# Bit_Reactor_modular_v1_0.net
KiCad netlist of a schematic drawn in EAGLE
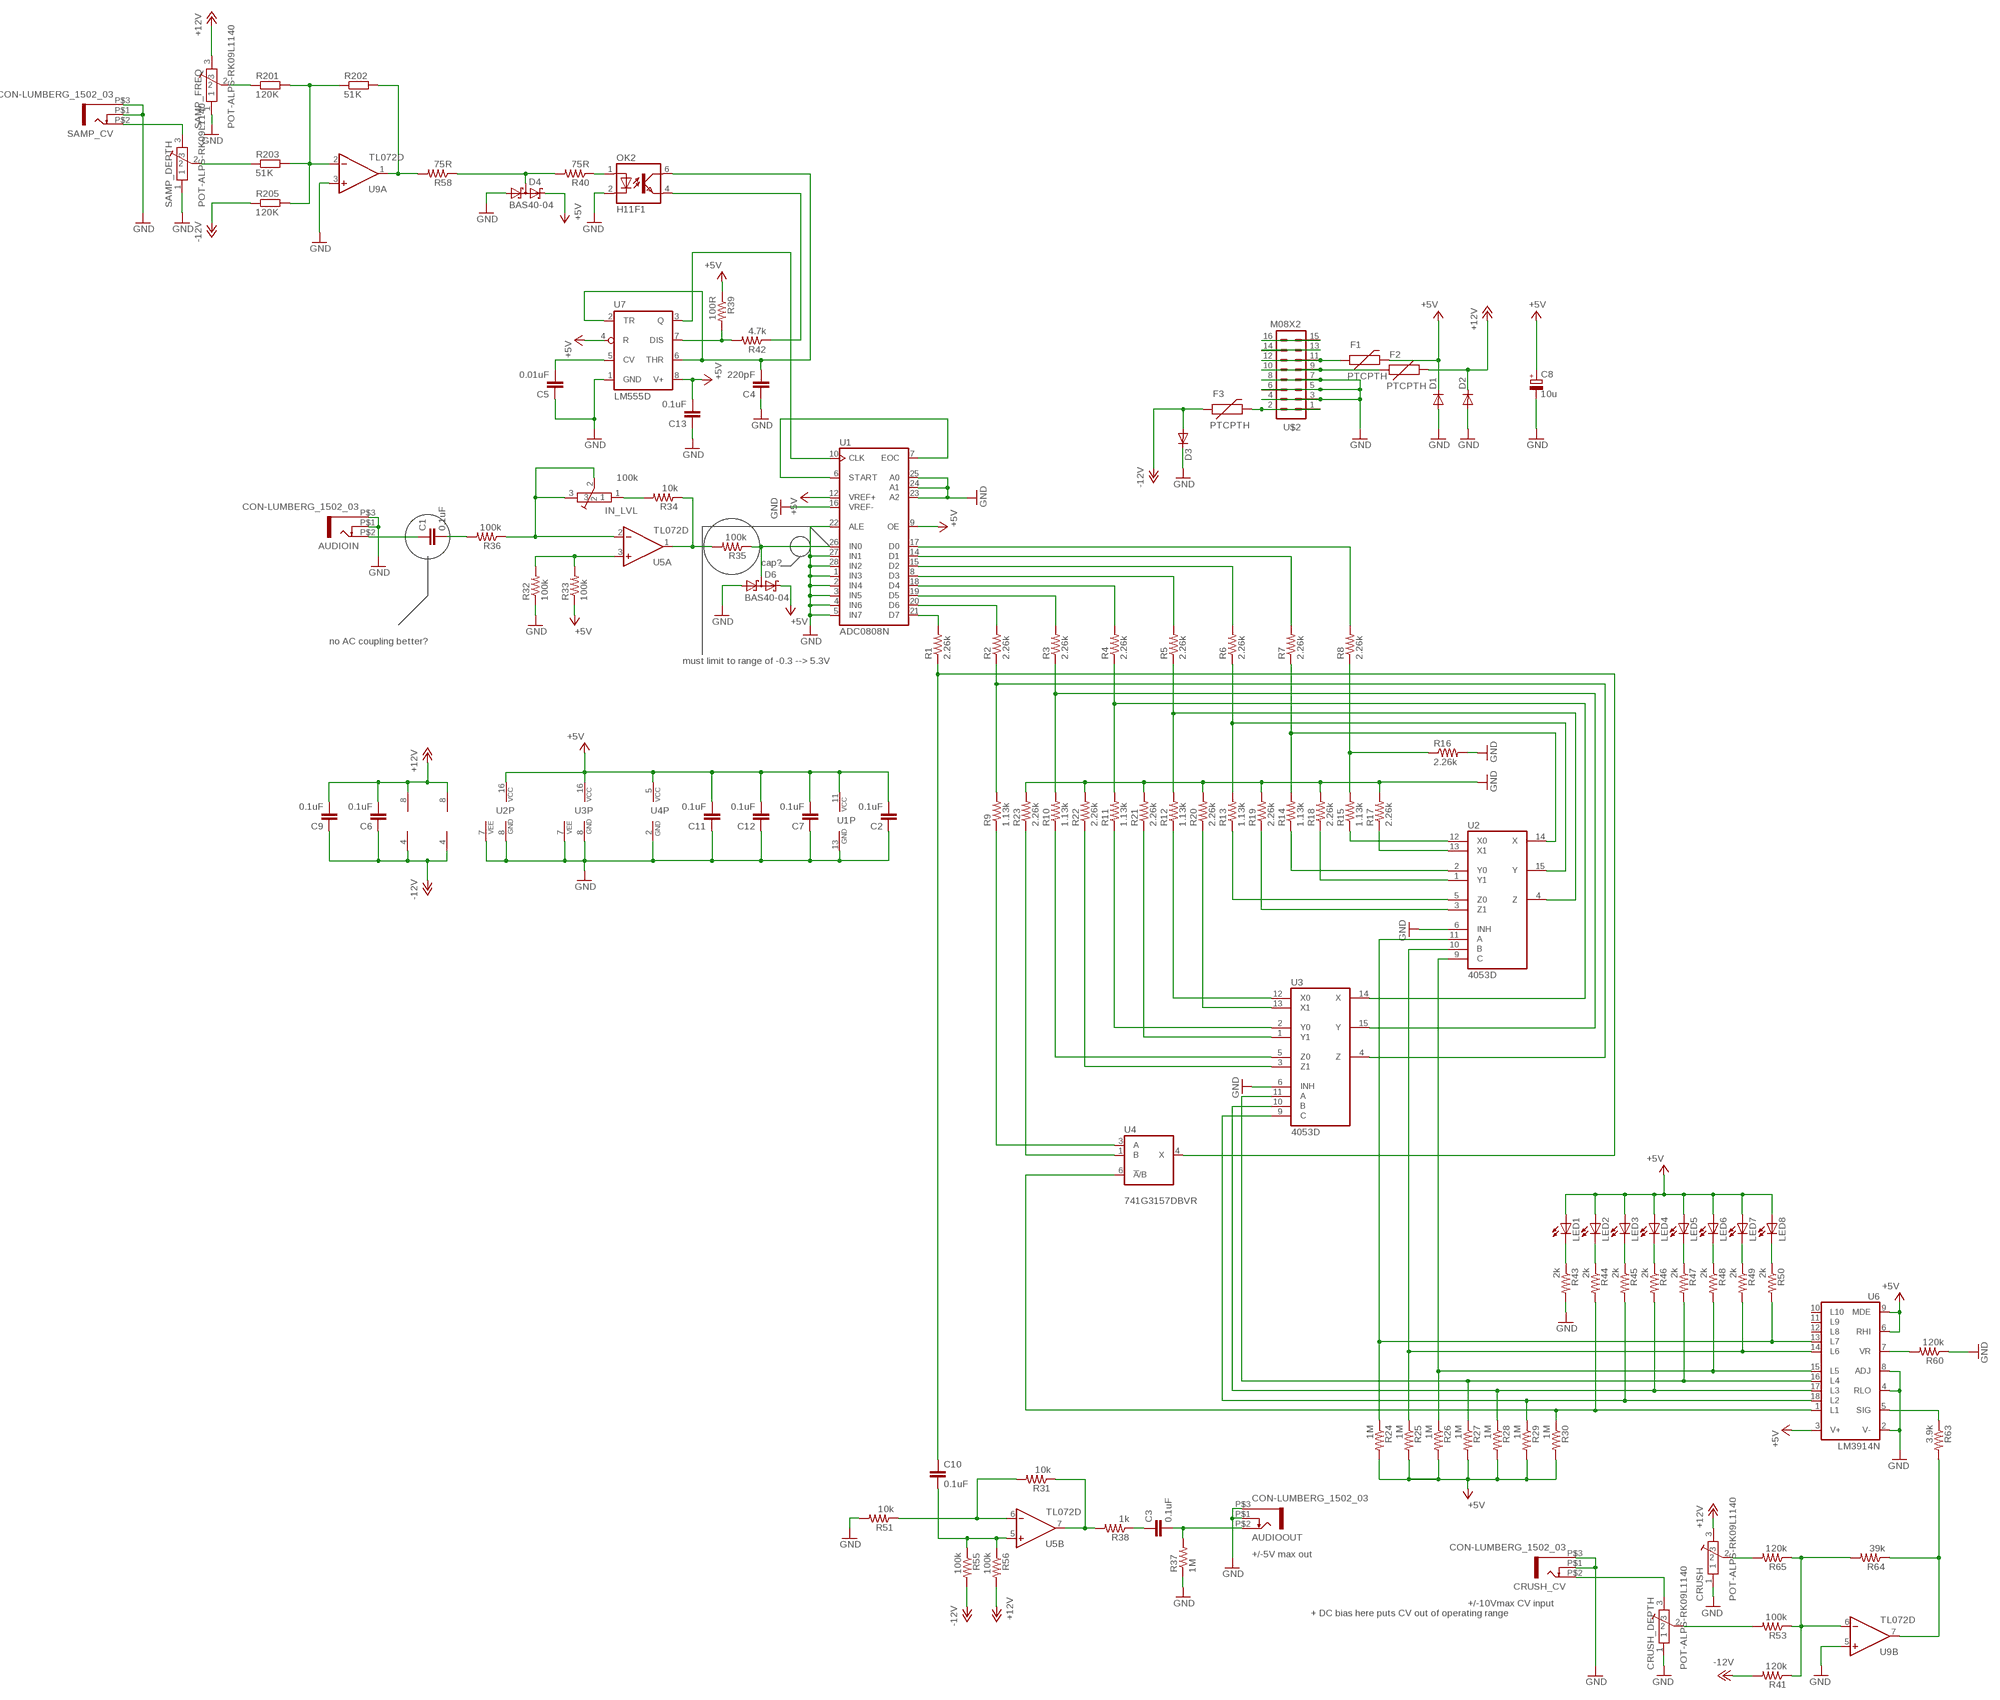
[diagram p0: schematic, sheet 1]

(export (version "E")
  (design (tool "Eeschema 10.0.6"))
  (components
    (comp (ref "AUDIOIN")
      (value "CON-LUMBERG_1502_03")
      (footprint "eagle-import:CON-LUMBERG_1502_03")
      (libsource (lib "eagle-import") (part "CON-LUMBERG_1502_03"))
    )
    (comp (ref "AUDIOOUT")
      (value "CON-LUMBERG_1502_03")
      (footprint "eagle-import:CON-LUMBERG_1502_03")
      (libsource (lib "eagle-import") (part "CON-LUMBERG_1502_03"))
    )
    (comp (ref "C1")
      (value "0.1uF")
      (footprint "eagle-import:C025-030X050")
      (libsource (lib "eagle-import") (part "C-EU025-030X050"))
    )
    (comp (ref "C2")
      (value "0.1uF")
      (footprint "eagle-import:C025-030X050")
      (libsource (lib "eagle-import") (part "C-EU025-030X050"))
    )
    (comp (ref "C3")
      (value "0.1uF")
      (footprint "eagle-import:C025-025X050")
      (libsource (lib "eagle-import") (part "C-EU025-025X050"))
    )
    (comp (ref "C4")
      (value "220pF")
      (footprint "eagle-import:C025-030X050")
      (libsource (lib "eagle-import") (part "C-EU025-030X050"))
    )
    (comp (ref "C5")
      (value "0.01uF")
      (footprint "eagle-import:C025-030X050")
      (libsource (lib "eagle-import") (part "C-EU025-030X050"))
    )
    (comp (ref "C6")
      (value "0.1uF")
      (footprint "eagle-import:C025-030X050")
      (libsource (lib "eagle-import") (part "C-EU025-030X050"))
    )
    (comp (ref "C7")
      (value "0.1uF")
      (footprint "eagle-import:C025-030X050")
      (libsource (lib "eagle-import") (part "C-EU025-030X050"))
    )
    (comp (ref "C8")
      (value "10u")
      (footprint "eagle-import:E5-6")
      (libsource (lib "eagle-import") (part "CPOL-EUE5-6"))
    )
    (comp (ref "C9")
      (value "0.1uF")
      (footprint "eagle-import:C025-030X050")
      (libsource (lib "eagle-import") (part "C-EU025-030X050"))
    )
    (comp (ref "C10")
      (value "0.1uF")
      (footprint "eagle-import:C025-030X050")
      (libsource (lib "eagle-import") (part "C-EU025-030X050"))
    )
    (comp (ref "C11")
      (value "0.1uF")
      (footprint "eagle-import:C025-030X050")
      (libsource (lib "eagle-import") (part "C-EU025-030X050"))
    )
    (comp (ref "C12")
      (value "0.1uF")
      (footprint "eagle-import:C025-030X050")
      (libsource (lib "eagle-import") (part "C-EU025-030X050"))
    )
    (comp (ref "C13")
      (value "0.1uF")
      (footprint "eagle-import:C025-030X050")
      (libsource (lib "eagle-import") (part "C-EU025-030X050"))
    )
    (comp (ref "CRUSH")
      (value "POT-ALPS-RK09L1140")
      (footprint "eagle-import:POT-ALPS-RK09L1140")
      (libsource (lib "eagle-import") (part "POT-ALPS-RK09L1140"))
    )
    (comp (ref "CRUSH_CV")
      (value "CON-LUMBERG_1502_03")
      (footprint "eagle-import:CON-LUMBERG_1502_03")
      (libsource (lib "eagle-import") (part "CON-LUMBERG_1502_03"))
    )
    (comp (ref "CRUSH_DEPTH")
      (value "POT-ALPS-RK09L1140")
      (footprint "eagle-import:POT-ALPS-RK09L1140")
      (libsource (lib "eagle-import") (part "POT-ALPS-RK09L1140"))
    )
    (comp (ref "D1")
      (value "DIODE1N4001")
      (footprint "eagle-import:DIODE-1N4001")
      (libsource (lib "eagle-import") (part "DIODE1N4001"))
    )
    (comp (ref "D2")
      (value "DIODE1N4001")
      (footprint "eagle-import:DIODE-1N4001")
      (libsource (lib "eagle-import") (part "DIODE1N4001"))
    )
    (comp (ref "D3")
      (value "DIODE1N4001")
      (footprint "eagle-import:DIODE-1N4001")
      (libsource (lib "eagle-import") (part "DIODE1N4001"))
    )
    (comp (ref "D4")
      (value "BAS40-04")
      (footprint "eagle-import:SOT23")
      (libsource (lib "eagle-import") (part "BAS40-04"))
    )
    (comp (ref "D6")
      (value "BAS40-04")
      (footprint "eagle-import:SOT23")
      (libsource (lib "eagle-import") (part "BAS40-04"))
    )
    (comp (ref "F1")
      (value "PTCPTH")
      (footprint "eagle-import:PTC")
      (libsource (lib "eagle-import") (part "PTCPTH"))
    )
    (comp (ref "F2")
      (value "PTCPTH")
      (footprint "eagle-import:PTC")
      (libsource (lib "eagle-import") (part "PTCPTH"))
    )
    (comp (ref "F3")
      (value "PTCPTH")
      (footprint "eagle-import:PTC")
      (libsource (lib "eagle-import") (part "PTCPTH"))
    )
    (comp (ref "IN_LVL")
      (value "100k")
      (footprint "eagle-import:POT-ALPS-RK09L1140")
      (libsource (lib "eagle-import") (part "POT-ALPS-RK09L1140"))
    )
    (comp (ref "LED1")
      (value "LED3MM")
      (footprint "eagle-import:LED3MM")
      (libsource (lib "eagle-import") (part "LED3MM"))
    )
    (comp (ref "LED2")
      (value "LED3MM")
      (footprint "eagle-import:LED3MM")
      (libsource (lib "eagle-import") (part "LED3MM"))
    )
    (comp (ref "LED3")
      (value "LED3MM")
      (footprint "eagle-import:LED3MM")
      (libsource (lib "eagle-import") (part "LED3MM"))
    )
    (comp (ref "LED4")
      (value "LED3MM")
      (footprint "eagle-import:LED3MM")
      (libsource (lib "eagle-import") (part "LED3MM"))
    )
    (comp (ref "LED5")
      (value "LED3MM")
      (footprint "eagle-import:LED3MM")
      (libsource (lib "eagle-import") (part "LED3MM"))
    )
    (comp (ref "LED6")
      (value "LED3MM")
      (footprint "eagle-import:LED3MM")
      (libsource (lib "eagle-import") (part "LED3MM"))
    )
    (comp (ref "LED7")
      (value "LED3MM")
      (footprint "eagle-import:LED3MM")
      (libsource (lib "eagle-import") (part "LED3MM"))
    )
    (comp (ref "LED8")
      (value "LED3MM")
      (footprint "eagle-import:LED3MM")
      (libsource (lib "eagle-import") (part "LED3MM"))
    )
    (comp (ref "OK2")
      (value "H11F1")
      (footprint "eagle-import:DIL05")
      (fields (field (name "OC_FARNELL") "unknown") (field (name "OC_NEWARK") "unknown"))
      (libsource (lib "eagle-import") (part "H11F1"))
    )
    (comp (ref "R1")
      (value "2.26k")
      (footprint "eagle-import:R0805W")
      (libsource (lib "eagle-import") (part "R-US_R0805W"))
    )
    (comp (ref "R2")
      (value "2.26k")
      (footprint "eagle-import:R0805W")
      (libsource (lib "eagle-import") (part "R-US_R0805W"))
    )
    (comp (ref "R3")
      (value "2.26k")
      (footprint "eagle-import:R0805W")
      (libsource (lib "eagle-import") (part "R-US_R0805W"))
    )
    (comp (ref "R4")
      (value "2.26k")
      (footprint "eagle-import:R0805W")
      (libsource (lib "eagle-import") (part "R-US_R0805W"))
    )
    (comp (ref "R5")
      (value "2.26k")
      (footprint "eagle-import:R0805W")
      (libsource (lib "eagle-import") (part "R-US_R0805W"))
    )
    (comp (ref "R6")
      (value "2.26k")
      (footprint "eagle-import:R0805W")
      (libsource (lib "eagle-import") (part "R-US_R0805W"))
    )
    (comp (ref "R7")
      (value "2.26k")
      (footprint "eagle-import:R0805W")
      (libsource (lib "eagle-import") (part "R-US_R0805W"))
    )
    (comp (ref "R8")
      (value "2.26k")
      (footprint "eagle-import:R0805W")
      (libsource (lib "eagle-import") (part "R-US_R0805W"))
    )
    (comp (ref "R9")
      (value "1.13k")
      (footprint "eagle-import:R0805W")
      (libsource (lib "eagle-import") (part "R-US_R0805W"))
    )
    (comp (ref "R10")
      (value "1.13k")
      (footprint "eagle-import:R0805W")
      (libsource (lib "eagle-import") (part "R-US_R0805W"))
    )
    (comp (ref "R11")
      (value "1.13k")
      (footprint "eagle-import:R0805W")
      (libsource (lib "eagle-import") (part "R-US_R0805W"))
    )
    (comp (ref "R12")
      (value "1.13k")
      (footprint "eagle-import:R0805W")
      (libsource (lib "eagle-import") (part "R-US_R0805W"))
    )
    (comp (ref "R13")
      (value "1.13k")
      (footprint "eagle-import:R0805W")
      (libsource (lib "eagle-import") (part "R-US_R0805W"))
    )
    (comp (ref "R14")
      (value "1.13k")
      (footprint "eagle-import:R0805W")
      (libsource (lib "eagle-import") (part "R-US_R0805W"))
    )
    (comp (ref "R15")
      (value "1.13k")
      (footprint "eagle-import:R0805W")
      (libsource (lib "eagle-import") (part "R-US_R0805W"))
    )
    (comp (ref "R16")
      (value "2.26k")
      (footprint "eagle-import:R0805W")
      (libsource (lib "eagle-import") (part "R-US_R0805W"))
    )
    (comp (ref "R17")
      (value "2.26k")
      (footprint "eagle-import:R0805W")
      (libsource (lib "eagle-import") (part "R-US_R0805W"))
    )
    (comp (ref "R18")
      (value "2.26k")
      (footprint "eagle-import:R0805W")
      (libsource (lib "eagle-import") (part "R-US_R0805W"))
    )
    (comp (ref "R19")
      (value "2.26k")
      (footprint "eagle-import:R0805W")
      (libsource (lib "eagle-import") (part "R-US_R0805W"))
    )
    (comp (ref "R20")
      (value "2.26k")
      (footprint "eagle-import:R0805W")
      (libsource (lib "eagle-import") (part "R-US_R0805W"))
    )
    (comp (ref "R21")
      (value "2.26k")
      (footprint "eagle-import:R0805W")
      (libsource (lib "eagle-import") (part "R-US_R0805W"))
    )
    (comp (ref "R22")
      (value "2.26k")
      (footprint "eagle-import:R0805W")
      (libsource (lib "eagle-import") (part "R-US_R0805W"))
    )
    (comp (ref "R23")
      (value "2.26k")
      (footprint "eagle-import:R0805W")
      (libsource (lib "eagle-import") (part "R-US_R0805W"))
    )
    (comp (ref "R24")
      (value "1M")
      (footprint "eagle-import:R0402")
      (libsource (lib "eagle-import") (part "R-US_R0402"))
    )
    (comp (ref "R25")
      (value "1M")
      (footprint "eagle-import:R0402")
      (libsource (lib "eagle-import") (part "R-US_R0402"))
    )
    (comp (ref "R26")
      (value "1M")
      (footprint "eagle-import:R0402")
      (libsource (lib "eagle-import") (part "R-US_R0402"))
    )
    (comp (ref "R27")
      (value "1M")
      (footprint "eagle-import:R0402")
      (libsource (lib "eagle-import") (part "R-US_R0402"))
    )
    (comp (ref "R28")
      (value "1M")
      (footprint "eagle-import:R0402")
      (libsource (lib "eagle-import") (part "R-US_R0402"))
    )
    (comp (ref "R29")
      (value "1M")
      (footprint "eagle-import:R0402")
      (libsource (lib "eagle-import") (part "R-US_R0402"))
    )
    (comp (ref "R30")
      (value "1M")
      (footprint "eagle-import:R0402")
      (libsource (lib "eagle-import") (part "R-US_R0402"))
    )
    (comp (ref "R31")
      (value "10k")
      (footprint "eagle-import:0207_10")
      (libsource (lib "eagle-import") (part "R-US_0207/10"))
    )
    (comp (ref "R32")
      (value "100k")
      (footprint "eagle-import:0207_10")
      (libsource (lib "eagle-import") (part "R-US_0207/10"))
    )
    (comp (ref "R33")
      (value "100k")
      (footprint "eagle-import:0207_10")
      (libsource (lib "eagle-import") (part "R-US_0207/10"))
    )
    (comp (ref "R34")
      (value "10k")
      (footprint "eagle-import:0207_10")
      (libsource (lib "eagle-import") (part "R-US_0207/10"))
    )
    (comp (ref "R35")
      (value "100k")
      (footprint "eagle-import:0207_10")
      (libsource (lib "eagle-import") (part "R-US_0207/10"))
    )
    (comp (ref "R36")
      (value "100k")
      (footprint "eagle-import:0207_10")
      (libsource (lib "eagle-import") (part "R-US_0207/10"))
    )
    (comp (ref "R37")
      (value "1M")
      (footprint "eagle-import:R0402")
      (libsource (lib "eagle-import") (part "R-US_R0402"))
    )
    (comp (ref "R38")
      (value "1k")
      (footprint "eagle-import:0207_10")
      (libsource (lib "eagle-import") (part "R-US_0207/10"))
    )
    (comp (ref "R39")
      (value "100R")
      (footprint "eagle-import:0207_10")
      (libsource (lib "eagle-import") (part "R-US_0207/10"))
    )
    (comp (ref "R40")
      (value "75R")
      (footprint "eagle-import:0207_10")
      (libsource (lib "eagle-import") (part "R-US_0207/10"))
    )
    (comp (ref "R41")
      (value "120k")
      (footprint "eagle-import:0207_10")
      (libsource (lib "eagle-import") (part "R-US_0207/10"))
    )
    (comp (ref "R42")
      (value "4.7k")
      (footprint "eagle-import:0207_10")
      (libsource (lib "eagle-import") (part "R-US_0207/10"))
    )
    (comp (ref "R43")
      (value "2k")
      (footprint "eagle-import:0207_7")
      (libsource (lib "eagle-import") (part "R-US_0207/7"))
    )
    (comp (ref "R44")
      (value "2k")
      (footprint "eagle-import:0207_7")
      (libsource (lib "eagle-import") (part "R-US_0207/7"))
    )
    (comp (ref "R45")
      (value "2k")
      (footprint "eagle-import:0207_7")
      (libsource (lib "eagle-import") (part "R-US_0207/7"))
    )
    (comp (ref "R46")
      (value "2k")
      (footprint "eagle-import:0207_7")
      (libsource (lib "eagle-import") (part "R-US_0207/7"))
    )
    (comp (ref "R47")
      (value "2k")
      (footprint "eagle-import:0207_7")
      (libsource (lib "eagle-import") (part "R-US_0207/7"))
    )
    (comp (ref "R48")
      (value "2k")
      (footprint "eagle-import:0207_10")
      (libsource (lib "eagle-import") (part "R-US_0207/10"))
    )
    (comp (ref "R49")
      (value "2k")
      (footprint "eagle-import:0207_7")
      (libsource (lib "eagle-import") (part "R-US_0207/7"))
    )
    (comp (ref "R50")
      (value "2k")
      (footprint "eagle-import:0207_7")
      (libsource (lib "eagle-import") (part "R-US_0207/7"))
    )
    (comp (ref "R51")
      (value "10k")
      (footprint "eagle-import:0207_10")
      (libsource (lib "eagle-import") (part "R-US_0207/10"))
    )
    (comp (ref "R53")
      (value "100k")
      (footprint "eagle-import:0207_10")
      (libsource (lib "eagle-import") (part "R-US_0207/10"))
    )
    (comp (ref "R55")
      (value "100k")
      (footprint "eagle-import:0207_10")
      (libsource (lib "eagle-import") (part "R-US_0207/10"))
    )
    (comp (ref "R56")
      (value "100k")
      (footprint "eagle-import:0207_10")
      (libsource (lib "eagle-import") (part "R-US_0207/10"))
    )
    (comp (ref "R58")
      (value "75R")
      (footprint "eagle-import:0207_10")
      (libsource (lib "eagle-import") (part "R-US_0207/10"))
    )
    (comp (ref "R60")
      (value "120k")
      (footprint "eagle-import:0207_10")
      (libsource (lib "eagle-import") (part "R-US_0207/10"))
    )
    (comp (ref "R63")
      (value "3.9k")
      (footprint "eagle-import:0207_10")
      (libsource (lib "eagle-import") (part "R-US_0207/10"))
    )
    (comp (ref "R64")
      (value "39k")
      (footprint "eagle-import:0207_10")
      (libsource (lib "eagle-import") (part "R-US_0207/10"))
    )
    (comp (ref "R65")
      (value "120k")
      (footprint "eagle-import:0207_10")
      (libsource (lib "eagle-import") (part "R-US_0207/10"))
    )
    (comp (ref "R201")
      (value "120K")
      (footprint "eagle-import:0204_7")
      (libsource (lib "eagle-import") (part "R-EU_0204/7"))
    )
    (comp (ref "R202")
      (value "51K")
      (footprint "eagle-import:0204_7")
      (libsource (lib "eagle-import") (part "R-EU_0204/7"))
    )
    (comp (ref "R203")
      (value "51K")
      (footprint "eagle-import:0204_7")
      (libsource (lib "eagle-import") (part "R-EU_0204/7"))
    )
    (comp (ref "R205")
      (value "120K")
      (footprint "eagle-import:0204_7")
      (libsource (lib "eagle-import") (part "R-EU_0204/7"))
    )
    (comp (ref "SAMP_CV")
      (value "CON-LUMBERG_1502_03")
      (footprint "eagle-import:CON-LUMBERG_1502_03")
      (libsource (lib "eagle-import") (part "CON-LUMBERG_1502_03"))
    )
    (comp (ref "SAMP_DEPTH")
      (value "POT-ALPS-RK09L1140")
      (footprint "eagle-import:POT-ALPS-RK09L1140")
      (libsource (lib "eagle-import") (part "POT-ALPS-RK09L1140"))
    )
    (comp (ref "SAMP_FREQ")
      (value "POT-ALPS-RK09L1140")
      (footprint "eagle-import:POT-ALPS-RK09L1140")
      (libsource (lib "eagle-import") (part "POT-ALPS-RK09L1140"))
    )
    (comp (ref "U$2")
      (value "M08X2")
      (footprint "eagle-import:2X8")
      (libsource (lib "eagle-import") (part "M08X2"))
    )
    (comp (ref "U1")
      (value "ADC0808N")
      (footprint "eagle-import:DIL28-6")
      (libsource (lib "eagle-import") (part "ADC0808N"))
    )
    (comp (ref "U2")
      (value "4053D")
      (footprint "eagle-import:SO16")
      (libsource (lib "eagle-import") (part "4053D"))
    )
    (comp (ref "U3")
      (value "4053D")
      (footprint "eagle-import:SO16")
      (libsource (lib "eagle-import") (part "4053D"))
    )
    (comp (ref "U4")
      (value "741G3157DBVR")
      (footprint "eagle-import:DBV_R-PDSO-G6")
      (libsource (lib "eagle-import") (part "741G3157DBVR"))
    )
    (comp (ref "U5")
      (value "TL072D")
      (footprint "eagle-import:SO08")
      (libsource (lib "eagle-import") (part "TL072D"))
    )
    (comp (ref "U6")
      (value "LM3914N")
      (footprint "eagle-import:DIL18")
      (libsource (lib "eagle-import") (part "LM3914N"))
    )
    (comp (ref "U7")
      (value "LM555D")
      (footprint "eagle-import:SO08")
      (libsource (lib "eagle-import") (part "555DLM"))
    )
    (comp (ref "U9")
      (value "TL072D")
      (footprint "eagle-import:SO08")
      (libsource (lib "eagle-import") (part "TL072D"))
    )
  )
  (nets
    (net (code "1") (name "+5V") (class "Default")
      (node (ref "C11") (pin "2") (pinfunction "2_2") (pintype "passive"))
      (node (ref "C12") (pin "2") (pinfunction "2_2") (pintype "passive"))
      (node (ref "C13") (pin "2") (pinfunction "2_2") (pintype "passive"))
      (node (ref "C2") (pin "2") (pinfunction "2_2") (pintype "passive"))
      (node (ref "C7") (pin "2") (pinfunction "2_2") (pintype "passive"))
      (node (ref "C8") (pin "+") (pinfunction "+_+") (pintype "passive"))
      (node (ref "D1") (pin "C") (pinfunction "C_C") (pintype "passive"))
      (node (ref "D4") (pin "2") (pinfunction "C2_2") (pintype "passive"))
      (node (ref "D6") (pin "2") (pinfunction "C2_2") (pintype "passive"))
      (node (ref "F1") (pin "P$2") (pinfunction "2_P$2") (pintype "bidirectional"))
      (node (ref "LED1") (pin "A") (pinfunction "A_A") (pintype "passive"))
      (node (ref "LED2") (pin "A") (pinfunction "A_A") (pintype "passive"))
      (node (ref "LED3") (pin "A") (pinfunction "A_A") (pintype "passive"))
      (node (ref "LED4") (pin "A") (pinfunction "A_A") (pintype "passive"))
      (node (ref "LED5") (pin "A") (pinfunction "A_A") (pintype "passive"))
      (node (ref "LED6") (pin "A") (pinfunction "A_A") (pintype "passive"))
      (node (ref "LED7") (pin "A") (pinfunction "A_A") (pintype "passive"))
      (node (ref "LED8") (pin "A") (pinfunction "A_A") (pintype "passive"))
      (node (ref "R24") (pin "2") (pinfunction "2_2") (pintype "passive"))
      (node (ref "R25") (pin "2") (pinfunction "2_2") (pintype "passive"))
      (node (ref "R26") (pin "2") (pinfunction "2_2") (pintype "passive"))
      (node (ref "R27") (pin "2") (pinfunction "2_2") (pintype "passive"))
      (node (ref "R28") (pin "2") (pinfunction "2_2") (pintype "passive"))
      (node (ref "R29") (pin "2") (pinfunction "2_2") (pintype "passive"))
      (node (ref "R30") (pin "2") (pinfunction "2_2") (pintype "passive"))
      (node (ref "R33") (pin "1") (pinfunction "1_1") (pintype "passive"))
      (node (ref "R39") (pin "1") (pinfunction "1_1") (pintype "passive"))
      (node (ref "U1") (pin "11") (pinfunction "VCC_11") (pintype "power_in"))
      (node (ref "U1") (pin "12") (pinfunction "VREF+_12") (pintype "input"))
      (node (ref "U1") (pin "9") (pinfunction "OE_9") (pintype "input"))
      (node (ref "U2") (pin "16") (pinfunction "VCC_16") (pintype "power_in"))
      (node (ref "U3") (pin "16") (pinfunction "VCC_16") (pintype "power_in"))
      (node (ref "U4") (pin "5") (pinfunction "VCC_5") (pintype "power_in"))
      (node (ref "U6") (pin "3") (pinfunction "V+_3") (pintype "power_in"))
      (node (ref "U6") (pin "6") (pinfunction "RHI_6") (pintype "input"))
      (node (ref "U6") (pin "9") (pinfunction "MDE_9") (pintype "input"))
      (node (ref "U7") (pin "4") (pinfunction "R_4") (pintype "input"))
      (node (ref "U7") (pin "8") (pinfunction "V+_8") (pintype "power_in"))
    )
    (net (code "2") (name "+12V") (class "Default")
      (node (ref "C6") (pin "2") (pinfunction "2_2") (pintype "passive"))
      (node (ref "C9") (pin "2") (pinfunction "2_2") (pintype "passive"))
      (node (ref "CRUSH") (pin "3") (pinfunction "3_3") (pintype "bidirectional"))
      (node (ref "D2") (pin "C") (pinfunction "C_C") (pintype "passive"))
      (node (ref "F2") (pin "P$2") (pinfunction "2_P$2") (pintype "bidirectional"))
      (node (ref "R56") (pin "2") (pinfunction "2_2") (pintype "passive"))
      (node (ref "SAMP_FREQ") (pin "3") (pinfunction "3_3") (pintype "bidirectional"))
      (node (ref "U5") (pin "8") (pinfunction "V+_8") (pintype "power_in"))
      (node (ref "U9") (pin "8") (pinfunction "V+_8") (pintype "power_in"))
    )
    (net (code "3") (name "-12V") (class "Default")
      (node (ref "C6") (pin "1") (pinfunction "1_1") (pintype "passive"))
      (node (ref "C9") (pin "1") (pinfunction "1_1") (pintype "passive"))
      (node (ref "D3") (pin "A") (pinfunction "A_A") (pintype "passive"))
      (node (ref "F3") (pin "P$1") (pinfunction "1_P$1") (pintype "bidirectional"))
      (node (ref "R205") (pin "1") (pinfunction "1_1") (pintype "passive"))
      (node (ref "R41") (pin "2") (pinfunction "2_2") (pintype "passive"))
      (node (ref "R55") (pin "2") (pinfunction "2_2") (pintype "passive"))
      (node (ref "U5") (pin "4") (pinfunction "V-_4") (pintype "power_in"))
      (node (ref "U9") (pin "4") (pinfunction "V-_4") (pintype "power_in"))
    )
    (net (code "4") (name "GND") (class "Default")
      (node (ref "AUDIOIN") (pin "P$1") (pinfunction "4_P$1") (pintype "passive"))
      (node (ref "AUDIOIN") (pin "P$3") (pinfunction "5_P$3") (pintype "passive"))
      (node (ref "AUDIOOUT") (pin "P$1") (pinfunction "4_P$1") (pintype "passive"))
      (node (ref "AUDIOOUT") (pin "P$3") (pinfunction "5_P$3") (pintype "passive"))
      (node (ref "C11") (pin "1") (pinfunction "1_1") (pintype "passive"))
      (node (ref "C12") (pin "1") (pinfunction "1_1") (pintype "passive"))
      (node (ref "C13") (pin "1") (pinfunction "1_1") (pintype "passive"))
      (node (ref "C2") (pin "1") (pinfunction "1_1") (pintype "passive"))
      (node (ref "C4") (pin "1") (pinfunction "1_1") (pintype "passive"))
      (node (ref "C5") (pin "1") (pinfunction "1_1") (pintype "passive"))
      (node (ref "C7") (pin "1") (pinfunction "1_1") (pintype "passive"))
      (node (ref "C8") (pin "-") (pinfunction "-_-") (pintype "passive"))
      (node (ref "CRUSH") (pin "1") (pinfunction "1_1") (pintype "bidirectional"))
      (node (ref "CRUSH_CV") (pin "P$1") (pinfunction "4_P$1") (pintype "passive"))
      (node (ref "CRUSH_CV") (pin "P$3") (pinfunction "5_P$3") (pintype "passive"))
      (node (ref "CRUSH_DEPTH") (pin "1") (pinfunction "1_1") (pintype "bidirectional"))
      (node (ref "D1") (pin "A") (pinfunction "A_A") (pintype "passive"))
      (node (ref "D2") (pin "A") (pinfunction "A_A") (pintype "passive"))
      (node (ref "D3") (pin "C") (pinfunction "C_C") (pintype "passive"))
      (node (ref "D4") (pin "1") (pinfunction "A1_1") (pintype "passive"))
      (node (ref "D6") (pin "1") (pinfunction "A1_1") (pintype "passive"))
      (node (ref "OK2") (pin "2") (pinfunction "C_2") (pintype "passive"))
      (node (ref "R16") (pin "2") (pinfunction "2_2") (pintype "passive"))
      (node (ref "R17") (pin "2") (pinfunction "2_2") (pintype "passive"))
      (node (ref "R18") (pin "2") (pinfunction "2_2") (pintype "passive"))
      (node (ref "R19") (pin "2") (pinfunction "2_2") (pintype "passive"))
      (node (ref "R20") (pin "2") (pinfunction "2_2") (pintype "passive"))
      (node (ref "R21") (pin "2") (pinfunction "2_2") (pintype "passive"))
      (node (ref "R22") (pin "2") (pinfunction "2_2") (pintype "passive"))
      (node (ref "R23") (pin "2") (pinfunction "2_2") (pintype "passive"))
      (node (ref "R32") (pin "1") (pinfunction "1_1") (pintype "passive"))
      (node (ref "R37") (pin "1") (pinfunction "1_1") (pintype "passive"))
      (node (ref "R43") (pin "2") (pinfunction "2_2") (pintype "passive"))
      (node (ref "R51") (pin "2") (pinfunction "2_2") (pintype "passive"))
      (node (ref "R60") (pin "1") (pinfunction "1_1") (pintype "passive"))
      (node (ref "SAMP_CV") (pin "P$1") (pinfunction "4_P$1") (pintype "passive"))
      (node (ref "SAMP_CV") (pin "P$3") (pinfunction "5_P$3") (pintype "passive"))
      (node (ref "SAMP_DEPTH") (pin "1") (pinfunction "1_1") (pintype "bidirectional"))
      (node (ref "SAMP_FREQ") (pin "1") (pinfunction "1_1") (pintype "bidirectional"))
      (node (ref "U$2") (pin "3") (pinfunction "3_3") (pintype "passive"))
      (node (ref "U$2") (pin "4") (pinfunction "4_4") (pintype "passive"))
      (node (ref "U$2") (pin "5") (pinfunction "5_5") (pintype "passive"))
      (node (ref "U$2") (pin "6") (pinfunction "6_6") (pintype "passive"))
      (node (ref "U$2") (pin "7") (pinfunction "7_7") (pintype "passive"))
      (node (ref "U$2") (pin "8") (pinfunction "8_8") (pintype "passive"))
      (node (ref "U1") (pin "1") (pinfunction "IN3_1") (pintype "input"))
      (node (ref "U1") (pin "13") (pinfunction "GND_13") (pintype "power_in"))
      (node (ref "U1") (pin "16") (pinfunction "VREF-_16") (pintype "input"))
      (node (ref "U1") (pin "2") (pinfunction "IN4_2") (pintype "input"))
      (node (ref "U1") (pin "22") (pinfunction "ALE_22") (pintype "input"))
      (node (ref "U1") (pin "23") (pinfunction "A2_23") (pintype "input"))
      (node (ref "U1") (pin "24") (pinfunction "A1_24") (pintype "input"))
      (node (ref "U1") (pin "25") (pinfunction "A0_25") (pintype "input"))
      (node (ref "U1") (pin "27") (pinfunction "IN1_27") (pintype "input"))
      (node (ref "U1") (pin "28") (pinfunction "IN2_28") (pintype "input"))
      (node (ref "U1") (pin "3") (pinfunction "IN5_3") (pintype "input"))
      (node (ref "U1") (pin "4") (pinfunction "IN6_4") (pintype "input"))
      (node (ref "U1") (pin "5") (pinfunction "IN7_5") (pintype "input"))
      (node (ref "U2") (pin "6") (pinfunction "INH_6") (pintype "input"))
      (node (ref "U2") (pin "7") (pinfunction "VEE_7") (pintype "power_in"))
      (node (ref "U2") (pin "8") (pinfunction "GND_8") (pintype "power_in"))
      (node (ref "U3") (pin "6") (pinfunction "INH_6") (pintype "input"))
      (node (ref "U3") (pin "7") (pinfunction "VEE_7") (pintype "power_in"))
      (node (ref "U3") (pin "8") (pinfunction "GND_8") (pintype "power_in"))
      (node (ref "U4") (pin "2") (pinfunction "GND_2") (pintype "power_in"))
      (node (ref "U6") (pin "2") (pinfunction "V-_2") (pintype "power_in"))
      (node (ref "U6") (pin "4") (pinfunction "RLO_4") (pintype "input"))
      (node (ref "U6") (pin "8") (pinfunction "ADJ_8") (pintype "input"))
      (node (ref "U7") (pin "1") (pinfunction "GND_1") (pintype "power_in"))
      (node (ref "U9") (pin "3") (pinfunction "+IN_3") (pintype "input"))
      (node (ref "U9") (pin "5") (pinfunction "+IN_5") (pintype "input"))
    )
    (net (code "5") (name "Net-(AUDIOIN-3)") (class "Default")
      (node (ref "AUDIOIN") (pin "P$2") (pinfunction "3_P$2") (pintype "passive"))
      (node (ref "C1") (pin "1") (pinfunction "1_1") (pintype "passive"))
    )
    (net (code "6") (name "Net-(AUDIOOUT-3)") (class "Default")
      (node (ref "AUDIOOUT") (pin "P$2") (pinfunction "3_P$2") (pintype "passive"))
      (node (ref "C3") (pin "2") (pinfunction "2_2") (pintype "passive"))
      (node (ref "R37") (pin "2") (pinfunction "2_2") (pintype "passive"))
    )
    (net (code "7") (name "Net-(C1-Pad2)") (class "Default")
      (node (ref "C1") (pin "2") (pinfunction "2_2") (pintype "passive"))
      (node (ref "R36") (pin "2") (pinfunction "2_2") (pintype "passive"))
    )
    (net (code "8") (name "Net-(C3-Pad1)") (class "Default")
      (node (ref "C3") (pin "1") (pinfunction "1_1") (pintype "passive"))
      (node (ref "R38") (pin "1") (pinfunction "1_1") (pintype "passive"))
    )
    (net (code "9") (name "Net-(CRUSH-Pad2)") (class "Default")
      (node (ref "CRUSH") (pin "2") (pinfunction "2_2") (pintype "bidirectional"))
      (node (ref "R65") (pin "2") (pinfunction "2_2") (pintype "passive"))
    )
    (net (code "10") (name "Net-(CRUSH_CV-3)") (class "Default")
      (node (ref "CRUSH_CV") (pin "P$2") (pinfunction "3_P$2") (pintype "passive"))
      (node (ref "CRUSH_DEPTH") (pin "3") (pinfunction "3_3") (pintype "bidirectional"))
    )
    (net (code "11") (name "Net-(CRUSH_DEPTH-Pad2)") (class "Default")
      (node (ref "CRUSH_DEPTH") (pin "2") (pinfunction "2_2") (pintype "bidirectional"))
      (node (ref "R53") (pin "2") (pinfunction "2_2") (pintype "passive"))
    )
    (net (code "12") (name "Net-(D4-C1A2)") (class "Default")
      (node (ref "D4") (pin "3") (pinfunction "C1A2_3") (pintype "passive"))
      (node (ref "R40") (pin "2") (pinfunction "2_2") (pintype "passive"))
      (node (ref "R58") (pin "1") (pinfunction "1_1") (pintype "passive"))
    )
    (net (code "13") (name "Net-(D6-C1A2)") (class "Default")
      (node (ref "D6") (pin "3") (pinfunction "C1A2_3") (pintype "passive"))
      (node (ref "R35") (pin "1") (pinfunction "1_1") (pintype "passive"))
      (node (ref "U1") (pin "26") (pinfunction "IN0_26") (pintype "input"))
    )
    (net (code "14") (name "Net-(F1-1)") (class "Default")
      (node (ref "F1") (pin "P$1") (pinfunction "1_P$1") (pintype "bidirectional"))
      (node (ref "U$2") (pin "11") (pinfunction "11_11") (pintype "passive"))
      (node (ref "U$2") (pin "12") (pinfunction "12_12") (pintype "passive"))
    )
    (net (code "15") (name "Net-(F2-1)") (class "Default")
      (node (ref "F2") (pin "P$1") (pinfunction "1_P$1") (pintype "bidirectional"))
      (node (ref "U$2") (pin "10") (pinfunction "10_10") (pintype "passive"))
      (node (ref "U$2") (pin "9") (pinfunction "9_9") (pintype "passive"))
    )
    (net (code "16") (name "Net-(F3-2)") (class "Default")
      (node (ref "F3") (pin "P$2") (pinfunction "2_P$2") (pintype "bidirectional"))
      (node (ref "U$2") (pin "1") (pinfunction "1_1") (pintype "passive"))
      (node (ref "U$2") (pin "2") (pinfunction "2_2") (pintype "passive"))
    )
    (net (code "17") (name "Net-(IN_LVL-Pad1)") (class "Default")
      (node (ref "IN_LVL") (pin "1") (pinfunction "1_1") (pintype "bidirectional"))
      (node (ref "R34") (pin "2") (pinfunction "2_2") (pintype "passive"))
    )
    (net (code "18") (name "Net-(LED1-C)") (class "Default")
      (node (ref "LED1") (pin "K") (pinfunction "C_K") (pintype "passive"))
      (node (ref "R43") (pin "1") (pinfunction "1_1") (pintype "passive"))
    )
    (net (code "19") (name "Net-(LED2-C)") (class "Default")
      (node (ref "LED2") (pin "K") (pinfunction "C_K") (pintype "passive"))
      (node (ref "R44") (pin "1") (pinfunction "1_1") (pintype "passive"))
    )
    (net (code "20") (name "Net-(LED3-C)") (class "Default")
      (node (ref "LED3") (pin "K") (pinfunction "C_K") (pintype "passive"))
      (node (ref "R45") (pin "1") (pinfunction "1_1") (pintype "passive"))
    )
    (net (code "21") (name "Net-(LED4-C)") (class "Default")
      (node (ref "LED4") (pin "K") (pinfunction "C_K") (pintype "passive"))
      (node (ref "R46") (pin "1") (pinfunction "1_1") (pintype "passive"))
    )
    (net (code "22") (name "Net-(LED5-C)") (class "Default")
      (node (ref "LED5") (pin "K") (pinfunction "C_K") (pintype "passive"))
      (node (ref "R47") (pin "1") (pinfunction "1_1") (pintype "passive"))
    )
    (net (code "23") (name "Net-(LED6-C)") (class "Default")
      (node (ref "LED6") (pin "K") (pinfunction "C_K") (pintype "passive"))
      (node (ref "R48") (pin "1") (pinfunction "1_1") (pintype "passive"))
    )
    (net (code "24") (name "Net-(LED7-C)") (class "Default")
      (node (ref "LED7") (pin "K") (pinfunction "C_K") (pintype "passive"))
      (node (ref "R49") (pin "1") (pinfunction "1_1") (pintype "passive"))
    )
    (net (code "25") (name "Net-(LED8-C)") (class "Default")
      (node (ref "LED8") (pin "K") (pinfunction "C_K") (pintype "passive"))
      (node (ref "R50") (pin "1") (pinfunction "1_1") (pintype "passive"))
    )
    (net (code "26") (name "Net-(OK2-A)") (class "Default")
      (node (ref "OK2") (pin "1") (pinfunction "A_1") (pintype "passive"))
      (node (ref "R40") (pin "1") (pinfunction "1_1") (pintype "passive"))
    )
    (net (code "27") (name "Net-(OK2-COL)") (class "Default")
      (node (ref "C4") (pin "2") (pinfunction "2_2") (pintype "passive"))
      (node (ref "OK2") (pin "6") (pinfunction "COL_6") (pintype "passive"))
      (node (ref "U7") (pin "2") (pinfunction "TR_2") (pintype "input"))
      (node (ref "U7") (pin "6") (pinfunction "THR_6") (pintype "input"))
    )
    (net (code "28") (name "Net-(OK2-EMIT)") (class "Default")
      (node (ref "OK2") (pin "4") (pinfunction "EMIT_4") (pintype "passive"))
      (node (ref "R42") (pin "1") (pinfunction "1_1") (pintype "passive"))
    )
    (net (code "29") (name "Net-(R15-Pad2)") (class "Default")
      (node (ref "R15") (pin "2") (pinfunction "2_2") (pintype "passive"))
      (node (ref "R16") (pin "1") (pinfunction "1_1") (pintype "passive"))
      (node (ref "R8") (pin "1") (pinfunction "1_1") (pintype "passive"))
    )
    (net (code "30") (name "Net-(R201-Pad1)") (class "Default")
      (node (ref "R201") (pin "1") (pinfunction "1_1") (pintype "passive"))
      (node (ref "SAMP_FREQ") (pin "2") (pinfunction "2_2") (pintype "bidirectional"))
    )
    (net (code "31") (name "Net-(R203-Pad1)") (class "Default")
      (node (ref "R203") (pin "1") (pinfunction "1_1") (pintype "passive"))
      (node (ref "SAMP_DEPTH") (pin "2") (pinfunction "2_2") (pintype "bidirectional"))
    )
    (net (code "32") (name "Net-(SAMP_CV-3)") (class "Default")
      (node (ref "SAMP_CV") (pin "P$2") (pinfunction "3_P$2") (pintype "passive"))
      (node (ref "SAMP_DEPTH") (pin "3") (pinfunction "3_3") (pintype "bidirectional"))
    )
    (net (code "33") (name "Net-(U$2-Pad13)") (class "Default")
      (node (ref "U$2") (pin "13") (pinfunction "13_13") (pintype "passive"))
      (node (ref "U$2") (pin "14") (pinfunction "14_14") (pintype "passive"))
    )
    (net (code "34") (name "Net-(U$2-Pad15)") (class "Default")
      (node (ref "U$2") (pin "15") (pinfunction "15_15") (pintype "passive"))
      (node (ref "U$2") (pin "16") (pinfunction "16_16") (pintype "passive"))
    )
    (net (code "35") (name "Net-(U1A-CLK)") (class "Default")
      (node (ref "U1") (pin "10") (pinfunction "CLK_10") (pintype "input"))
      (node (ref "U7") (pin "3") (pinfunction "Q_3") (pintype "output"))
    )
    (net (code "36") (name "Net-(U1A-D0)") (class "Default")
      (node (ref "R8") (pin "2") (pinfunction "2_2") (pintype "passive"))
      (node (ref "U1") (pin "17") (pinfunction "D0_17") (pintype "tri_state"))
    )
    (net (code "37") (name "Net-(U1A-D1)") (class "Default")
      (node (ref "R7") (pin "2") (pinfunction "2_2") (pintype "passive"))
      (node (ref "U1") (pin "14") (pinfunction "D1_14") (pintype "tri_state"))
    )
    (net (code "38") (name "Net-(U1A-D2)") (class "Default")
      (node (ref "R6") (pin "2") (pinfunction "2_2") (pintype "passive"))
      (node (ref "U1") (pin "15") (pinfunction "D2_15") (pintype "tri_state"))
    )
    (net (code "39") (name "Net-(U1A-D3)") (class "Default")
      (node (ref "R5") (pin "2") (pinfunction "2_2") (pintype "passive"))
      (node (ref "U1") (pin "8") (pinfunction "D3_8") (pintype "tri_state"))
    )
    (net (code "40") (name "Net-(U1A-D4)") (class "Default")
      (node (ref "R4") (pin "2") (pinfunction "2_2") (pintype "passive"))
      (node (ref "U1") (pin "18") (pinfunction "D4_18") (pintype "tri_state"))
    )
    (net (code "41") (name "Net-(U1A-D5)") (class "Default")
      (node (ref "R3") (pin "2") (pinfunction "2_2") (pintype "passive"))
      (node (ref "U1") (pin "19") (pinfunction "D5_19") (pintype "tri_state"))
    )
    (net (code "42") (name "Net-(U1A-D6)") (class "Default")
      (node (ref "R2") (pin "2") (pinfunction "2_2") (pintype "passive"))
      (node (ref "U1") (pin "20") (pinfunction "D6_20") (pintype "tri_state"))
    )
    (net (code "43") (name "Net-(U1A-D7)") (class "Default")
      (node (ref "R1") (pin "2") (pinfunction "2_2") (pintype "passive"))
      (node (ref "U1") (pin "21") (pinfunction "D7_21") (pintype "tri_state"))
    )
    (net (code "44") (name "Net-(U1A-EOC)") (class "Default")
      (node (ref "U1") (pin "6") (pinfunction "START_6") (pintype "input"))
      (node (ref "U1") (pin "7") (pinfunction "EOC_7") (pintype "output"))
    )
    (net (code "45") (name "Net-(U2A-A)") (class "Default")
      (node (ref "R24") (pin "1") (pinfunction "1_1") (pintype "passive"))
      (node (ref "R50") (pin "2") (pinfunction "2_2") (pintype "passive"))
      (node (ref "U2") (pin "11") (pinfunction "A_11") (pintype "input"))
      (node (ref "U6") (pin "13") (pinfunction "L7_13") (pintype "output"))
    )
    (net (code "46") (name "Net-(U2A-B)") (class "Default")
      (node (ref "R25") (pin "1") (pinfunction "1_1") (pintype "passive"))
      (node (ref "R49") (pin "2") (pinfunction "2_2") (pintype "passive"))
      (node (ref "U2") (pin "10") (pinfunction "B_10") (pintype "input"))
      (node (ref "U6") (pin "14") (pinfunction "L6_14") (pintype "output"))
    )
    (net (code "47") (name "Net-(U2A-C)") (class "Default")
      (node (ref "R26") (pin "1") (pinfunction "1_1") (pintype "passive"))
      (node (ref "R48") (pin "2") (pinfunction "2_2") (pintype "passive"))
      (node (ref "U2") (pin "9") (pinfunction "C_9") (pintype "input"))
      (node (ref "U6") (pin "15") (pinfunction "L5_15") (pintype "output"))
    )
    (net (code "48") (name "Net-(U2A-X)") (class "Default")
      (node (ref "R14") (pin "2") (pinfunction "2_2") (pintype "passive"))
      (node (ref "R7") (pin "1") (pinfunction "1_1") (pintype "passive"))
      (node (ref "U2") (pin "14") (pinfunction "X_14") (pintype "bidirectional"))
    )
    (net (code "49") (name "Net-(U2A-X0)") (class "Default")
      (node (ref "R15") (pin "1") (pinfunction "1_1") (pintype "passive"))
      (node (ref "U2") (pin "12") (pinfunction "X0_12") (pintype "bidirectional"))
    )
    (net (code "50") (name "Net-(U2A-X1)") (class "Default")
      (node (ref "R17") (pin "1") (pinfunction "1_1") (pintype "passive"))
      (node (ref "U2") (pin "13") (pinfunction "X1_13") (pintype "bidirectional"))
    )
    (net (code "51") (name "Net-(U2A-Y)") (class "Default")
      (node (ref "R13") (pin "2") (pinfunction "2_2") (pintype "passive"))
      (node (ref "R6") (pin "1") (pinfunction "1_1") (pintype "passive"))
      (node (ref "U2") (pin "15") (pinfunction "Y_15") (pintype "bidirectional"))
    )
    (net (code "52") (name "Net-(U2A-Y0)") (class "Default")
      (node (ref "R14") (pin "1") (pinfunction "1_1") (pintype "passive"))
      (node (ref "U2") (pin "2") (pinfunction "Y0_2") (pintype "bidirectional"))
    )
    (net (code "53") (name "Net-(U2A-Y1)") (class "Default")
      (node (ref "R18") (pin "1") (pinfunction "1_1") (pintype "passive"))
      (node (ref "U2") (pin "1") (pinfunction "Y1_1") (pintype "bidirectional"))
    )
    (net (code "54") (name "Net-(U2A-Z)") (class "Default")
      (node (ref "R12") (pin "2") (pinfunction "2_2") (pintype "passive"))
      (node (ref "R5") (pin "1") (pinfunction "1_1") (pintype "passive"))
      (node (ref "U2") (pin "4") (pinfunction "Z_4") (pintype "bidirectional"))
    )
    (net (code "55") (name "Net-(U2A-Z0)") (class "Default")
      (node (ref "R13") (pin "1") (pinfunction "1_1") (pintype "passive"))
      (node (ref "U2") (pin "5") (pinfunction "Z0_5") (pintype "bidirectional"))
    )
    (net (code "56") (name "Net-(U2A-Z1)") (class "Default")
      (node (ref "R19") (pin "1") (pinfunction "1_1") (pintype "passive"))
      (node (ref "U2") (pin "3") (pinfunction "Z1_3") (pintype "bidirectional"))
    )
    (net (code "57") (name "Net-(U3A-A)") (class "Default")
      (node (ref "R27") (pin "1") (pinfunction "1_1") (pintype "passive"))
      (node (ref "R47") (pin "2") (pinfunction "2_2") (pintype "passive"))
      (node (ref "U3") (pin "11") (pinfunction "A_11") (pintype "input"))
      (node (ref "U6") (pin "16") (pinfunction "L4_16") (pintype "output"))
    )
    (net (code "58") (name "Net-(U3A-B)") (class "Default")
      (node (ref "R28") (pin "1") (pinfunction "1_1") (pintype "passive"))
      (node (ref "R46") (pin "2") (pinfunction "2_2") (pintype "passive"))
      (node (ref "U3") (pin "10") (pinfunction "B_10") (pintype "input"))
      (node (ref "U6") (pin "17") (pinfunction "L3_17") (pintype "output"))
    )
    (net (code "59") (name "Net-(U3A-C)") (class "Default")
      (node (ref "R29") (pin "1") (pinfunction "1_1") (pintype "passive"))
      (node (ref "R45") (pin "2") (pinfunction "2_2") (pintype "passive"))
      (node (ref "U3") (pin "9") (pinfunction "C_9") (pintype "input"))
      (node (ref "U6") (pin "18") (pinfunction "L2_18") (pintype "output"))
    )
    (net (code "60") (name "Net-(U3A-X)") (class "Default")
      (node (ref "R11") (pin "2") (pinfunction "2_2") (pintype "passive"))
      (node (ref "R4") (pin "1") (pinfunction "1_1") (pintype "passive"))
      (node (ref "U3") (pin "14") (pinfunction "X_14") (pintype "bidirectional"))
    )
    (net (code "61") (name "Net-(U3A-X0)") (class "Default")
      (node (ref "R12") (pin "1") (pinfunction "1_1") (pintype "passive"))
      (node (ref "U3") (pin "12") (pinfunction "X0_12") (pintype "bidirectional"))
    )
    (net (code "62") (name "Net-(U3A-X1)") (class "Default")
      (node (ref "R20") (pin "1") (pinfunction "1_1") (pintype "passive"))
      (node (ref "U3") (pin "13") (pinfunction "X1_13") (pintype "bidirectional"))
    )
    (net (code "63") (name "Net-(U3A-Y)") (class "Default")
      (node (ref "R10") (pin "2") (pinfunction "2_2") (pintype "passive"))
      (node (ref "R3") (pin "1") (pinfunction "1_1") (pintype "passive"))
      (node (ref "U3") (pin "15") (pinfunction "Y_15") (pintype "bidirectional"))
    )
    (net (code "64") (name "Net-(U3A-Y0)") (class "Default")
      (node (ref "R11") (pin "1") (pinfunction "1_1") (pintype "passive"))
      (node (ref "U3") (pin "2") (pinfunction "Y0_2") (pintype "bidirectional"))
    )
    (net (code "65") (name "Net-(U3A-Y1)") (class "Default")
      (node (ref "R21") (pin "1") (pinfunction "1_1") (pintype "passive"))
      (node (ref "U3") (pin "1") (pinfunction "Y1_1") (pintype "bidirectional"))
    )
    (net (code "66") (name "Net-(U3A-Z)") (class "Default")
      (node (ref "R2") (pin "1") (pinfunction "1_1") (pintype "passive"))
      (node (ref "R9") (pin "2") (pinfunction "2_2") (pintype "passive"))
      (node (ref "U3") (pin "4") (pinfunction "Z_4") (pintype "bidirectional"))
    )
    (net (code "67") (name "Net-(U3A-Z0)") (class "Default")
      (node (ref "R10") (pin "1") (pinfunction "1_1") (pintype "passive"))
      (node (ref "U3") (pin "5") (pinfunction "Z0_5") (pintype "bidirectional"))
    )
    (net (code "68") (name "Net-(U3A-Z1)") (class "Default")
      (node (ref "R22") (pin "1") (pinfunction "1_1") (pintype "passive"))
      (node (ref "U3") (pin "3") (pinfunction "Z1_3") (pintype "bidirectional"))
    )
    (net (code "69") (name "Net-(U4A-A)") (class "Default")
      (node (ref "R9") (pin "1") (pinfunction "1_1") (pintype "passive"))
      (node (ref "U4") (pin "3") (pinfunction "A_3") (pintype "bidirectional"))
    )
    (net (code "70") (name "Net-(U4A-B)") (class "Default")
      (node (ref "R23") (pin "1") (pinfunction "1_1") (pintype "passive"))
      (node (ref "U4") (pin "1") (pinfunction "B_1") (pintype "bidirectional"))
    )
    (net (code "71") (name "Net-(U4A-X)") (class "Default")
      (node (ref "C10") (pin "1") (pinfunction "1_1") (pintype "passive"))
      (node (ref "R1") (pin "1") (pinfunction "1_1") (pintype "passive"))
      (node (ref "U4") (pin "4") (pinfunction "X_4") (pintype "bidirectional"))
    )
    (net (code "72") (name "Net-(U4A-~{A}{slash}B)") (class "Default")
      (node (ref "R30") (pin "1") (pinfunction "1_1") (pintype "passive"))
      (node (ref "R44") (pin "2") (pinfunction "2_2") (pintype "passive"))
      (node (ref "U4") (pin "6") (pinfunction "~{A}/B_6") (pintype "input"))
      (node (ref "U6") (pin "1") (pinfunction "L1_1") (pintype "output"))
    )
    (net (code "73") (name "Net-(U5A-+IN)") (class "Default")
      (node (ref "R32") (pin "2") (pinfunction "2_2") (pintype "passive"))
      (node (ref "R33") (pin "2") (pinfunction "2_2") (pintype "passive"))
      (node (ref "U5") (pin "3") (pinfunction "+IN_3") (pintype "input"))
    )
    (net (code "74") (name "Net-(U5A--IN)") (class "Default")
      (node (ref "IN_LVL") (pin "2") (pinfunction "2_2") (pintype "bidirectional"))
      (node (ref "IN_LVL") (pin "3") (pinfunction "3_3") (pintype "bidirectional"))
      (node (ref "R36") (pin "1") (pinfunction "1_1") (pintype "passive"))
      (node (ref "U5") (pin "2") (pinfunction "-IN_2") (pintype "input"))
    )
    (net (code "75") (name "Net-(U5A-OUT)") (class "Default")
      (node (ref "R34") (pin "1") (pinfunction "1_1") (pintype "passive"))
      (node (ref "R35") (pin "2") (pinfunction "2_2") (pintype "passive"))
      (node (ref "U5") (pin "1") (pinfunction "OUT_1") (pintype "output"))
    )
    (net (code "76") (name "Net-(U5B-+IN)") (class "Default")
      (node (ref "C10") (pin "2") (pinfunction "2_2") (pintype "passive"))
      (node (ref "R55") (pin "1") (pinfunction "1_1") (pintype "passive"))
      (node (ref "R56") (pin "1") (pinfunction "1_1") (pintype "passive"))
      (node (ref "U5") (pin "5") (pinfunction "+IN_5") (pintype "input"))
    )
    (net (code "77") (name "Net-(U5B--IN)") (class "Default")
      (node (ref "R31") (pin "2") (pinfunction "2_2") (pintype "passive"))
      (node (ref "R51") (pin "1") (pinfunction "1_1") (pintype "passive"))
      (node (ref "U5") (pin "6") (pinfunction "-IN_6") (pintype "input"))
    )
    (net (code "78") (name "Net-(U5B-OUT)") (class "Default")
      (node (ref "R31") (pin "1") (pinfunction "1_1") (pintype "passive"))
      (node (ref "R38") (pin "2") (pinfunction "2_2") (pintype "passive"))
      (node (ref "U5") (pin "7") (pinfunction "OUT_7") (pintype "output"))
    )
    (net (code "79") (name "Net-(U6-SIG)") (class "Default")
      (node (ref "R63") (pin "1") (pinfunction "1_1") (pintype "passive"))
      (node (ref "U6") (pin "5") (pinfunction "SIG_5") (pintype "input"))
    )
    (net (code "80") (name "Net-(U6-VR)") (class "Default")
      (node (ref "R60") (pin "2") (pinfunction "2_2") (pintype "passive"))
      (node (ref "U6") (pin "7") (pinfunction "VR_7") (pintype "output"))
    )
    (net (code "81") (name "Net-(U7-CV)") (class "Default")
      (node (ref "C5") (pin "2") (pinfunction "2_2") (pintype "passive"))
      (node (ref "U7") (pin "5") (pinfunction "CV_5") (pintype "input"))
    )
    (net (code "82") (name "Net-(U7-DIS)") (class "Default")
      (node (ref "R39") (pin "2") (pinfunction "2_2") (pintype "passive"))
      (node (ref "R42") (pin "2") (pinfunction "2_2") (pintype "passive"))
      (node (ref "U7") (pin "7") (pinfunction "DIS_7") (pintype "input"))
    )
    (net (code "83") (name "Net-(U9A--IN)") (class "Default")
      (node (ref "R201") (pin "2") (pinfunction "2_2") (pintype "passive"))
      (node (ref "R202") (pin "1") (pinfunction "1_1") (pintype "passive"))
      (node (ref "R203") (pin "2") (pinfunction "2_2") (pintype "passive"))
      (node (ref "R205") (pin "2") (pinfunction "2_2") (pintype "passive"))
      (node (ref "U9") (pin "2") (pinfunction "-IN_2") (pintype "input"))
    )
    (net (code "84") (name "Net-(U9A-OUT)") (class "Default")
      (node (ref "R202") (pin "2") (pinfunction "2_2") (pintype "passive"))
      (node (ref "R58") (pin "2") (pinfunction "2_2") (pintype "passive"))
      (node (ref "U9") (pin "1") (pinfunction "OUT_1") (pintype "output"))
    )
    (net (code "85") (name "Net-(U9B--IN)") (class "Default")
      (node (ref "R41") (pin "1") (pinfunction "1_1") (pintype "passive"))
      (node (ref "R53") (pin "1") (pinfunction "1_1") (pintype "passive"))
      (node (ref "R64") (pin "2") (pinfunction "2_2") (pintype "passive"))
      (node (ref "R65") (pin "1") (pinfunction "1_1") (pintype "passive"))
      (node (ref "U9") (pin "6") (pinfunction "-IN_6") (pintype "input"))
    )
    (net (code "86") (name "Net-(U9B-OUT)") (class "Default")
      (node (ref "R63") (pin "2") (pinfunction "2_2") (pintype "passive"))
      (node (ref "R64") (pin "1") (pinfunction "1_1") (pintype "passive"))
      (node (ref "U9") (pin "7") (pinfunction "OUT_7") (pintype "output"))
    )
    (net (code "87") (name "unconnected-(U6-L8-Pad12)") (class "Default")
      (node (ref "U6") (pin "12") (pinfunction "L8_12") (pintype "output"))
    )
    (net (code "88") (name "unconnected-(U6-L9-Pad11)") (class "Default")
      (node (ref "U6") (pin "11") (pinfunction "L9_11") (pintype "output"))
    )
    (net (code "89") (name "unconnected-(U6-L10-Pad10)") (class "Default")
      (node (ref "U6") (pin "10") (pinfunction "L10_10") (pintype "output"))
    )
  )
)
